# auxboxshield1_54.net
KiCad netlist of a schematic drawn in EAGLE
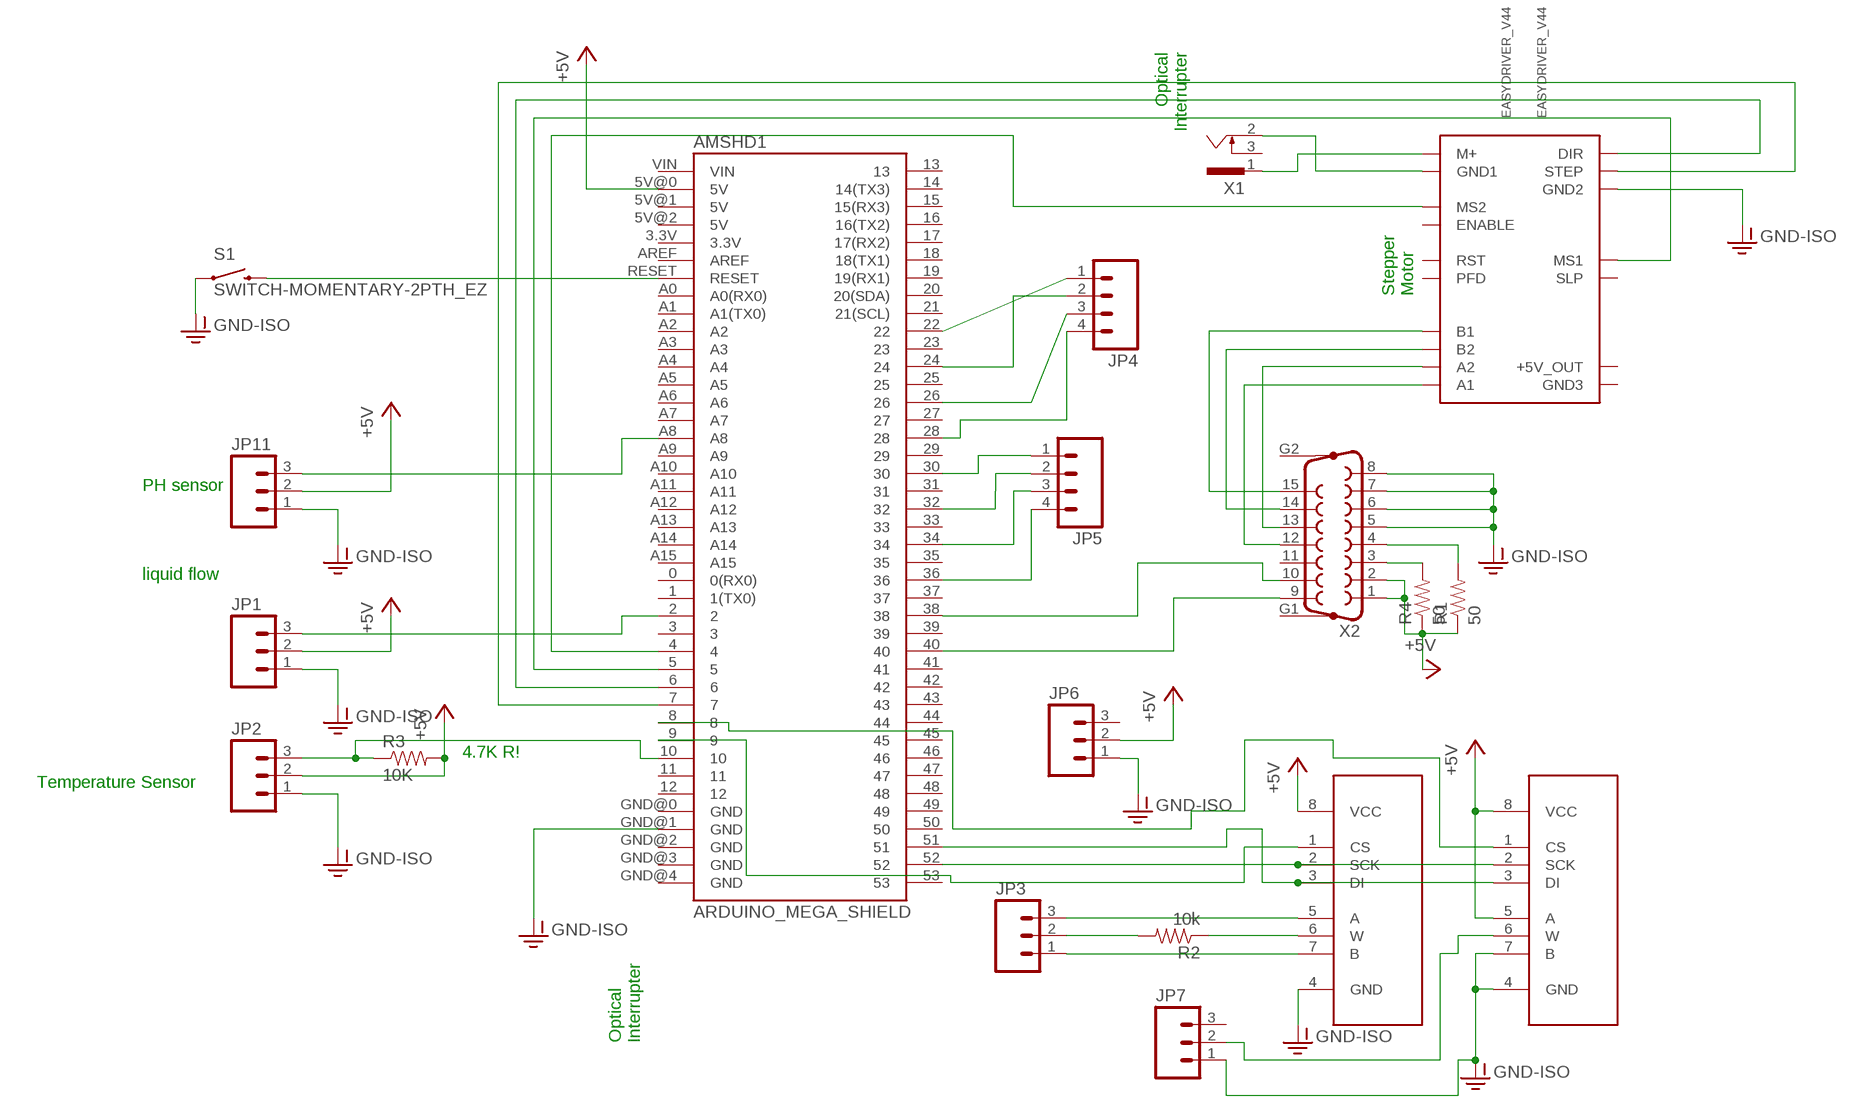
[diagram p0: schematic, sheet 1]

(export (version "E")
  (design (tool "Eeschema 10.0.6"))
  (components
    (comp (ref "AMSHD1")
      (value "ARDUINO_MEGA_SHIELD")
      (footprint "eagle-import:ARDUINO_MEGA_SHIELD")
      (libsource (lib "eagle-import") (part "ARDUINO_MEGA_SHIELD"))
    )
    (comp (ref "EASYDRIVER_V44")
      (value "EASYDRIVER_V44")
      (footprint "eagle-import:EASYDRIVER_V44")
      (libsource (lib "eagle-import") (part "EASYDRIVER_V44"))
    )
    (comp (ref "JP1")
      (value "M03POLAR")
      (footprint "eagle-import:MOLEX-1X3")
      (libsource (lib "eagle-import") (part "M03POLAR"))
    )
    (comp (ref "JP2")
      (value "M03POLAR")
      (footprint "eagle-import:MOLEX-1X3")
      (libsource (lib "eagle-import") (part "M03POLAR"))
    )
    (comp (ref "JP3")
      (value "M03POLAR")
      (footprint "eagle-import:MOLEX-1X3")
      (libsource (lib "eagle-import") (part "M03POLAR"))
    )
    (comp (ref "JP4")
      (value "M04POLAR")
      (footprint "eagle-import:MOLEX-1X4")
      (libsource (lib "eagle-import") (part "M04POLAR"))
    )
    (comp (ref "JP5")
      (value "M04POLAR")
      (footprint "eagle-import:MOLEX-1X4")
      (libsource (lib "eagle-import") (part "M04POLAR"))
    )
    (comp (ref "JP6")
      (value "M03POLAR")
      (footprint "eagle-import:MOLEX-1X3")
      (libsource (lib "eagle-import") (part "M03POLAR"))
    )
    (comp (ref "JP7")
      (value "M03POLAR")
      (footprint "eagle-import:MOLEX-1X3")
      (libsource (lib "eagle-import") (part "M03POLAR"))
    )
    (comp (ref "JP11")
      (value "M03POLAR")
      (footprint "eagle-import:MOLEX-1X3")
      (libsource (lib "eagle-import") (part "M03POLAR"))
    )
    (comp (ref "R1")
      (value "50")
      (footprint "eagle-import:AXIAL-0.3")
      (libsource (lib "eagle-import") (part "10OHM-1/4W-5%(PTH)"))
    )
    (comp (ref "R2")
      (value "10k")
      (footprint "eagle-import:AXIAL-0.3")
      (libsource (lib "eagle-import") (part "10KOHM-1/4W-1%(PTH)HORIZ"))
    )
    (comp (ref "R3")
      (value "10K")
      (footprint "eagle-import:AXIAL-0.3")
      (libsource (lib "eagle-import") (part "10OHM-1/4W-5%(PTH)"))
    )
    (comp (ref "R4")
      (value "50")
      (footprint "eagle-import:AXIAL-0.3")
      (libsource (lib "eagle-import") (part "10OHM-1/4W-5%(PTH)"))
    )
    (comp (ref "S1")
      (value "SWITCH-MOMENTARY-2PTH_EZ")
      (footprint "eagle-import:TACTILE-PTH-EZ")
      (libsource (lib "eagle-import") (part "SWITCH-MOMENTARY-2PTH_EZ"))
    )
    (comp (ref "U1")
      (value "MCP41XXXDIL")
      (footprint "eagle-import:DIL-08")
      (libsource (lib "eagle-import") (part "MCP41XXXDIL"))
    )
    (comp (ref "U2")
      (value "MCP41XXXDIL")
      (footprint "eagle-import:DIL-08")
      (libsource (lib "eagle-import") (part "MCP41XXXDIL"))
    )
    (comp (ref "X1")
      (value "SCD-014A")
      (footprint "eagle-import:SCD-014-A")
      (libsource (lib "eagle-import") (part "SCD-014A"))
    )
    (comp (ref "X2")
      (value "F15VP")
      (footprint "eagle-import:F15VP")
      (libsource (lib "eagle-import") (part "F15VP"))
    )
  )
  (nets
    (net (code "1") (name "+5V") (class "Default")
      (node (ref "AMSHD1") (pin "5V@0") (pinfunction "5V_5V@0") (pintype "bidirectional"))
      (node (ref "JP1") (pin "2") (pinfunction "2_2") (pintype "passive"))
      (node (ref "JP11") (pin "2") (pinfunction "2_2") (pintype "passive"))
      (node (ref "JP2") (pin "2") (pinfunction "2_2") (pintype "passive"))
      (node (ref "JP6") (pin "2") (pinfunction "2_2") (pintype "passive"))
      (node (ref "R1") (pin "P$1") (pinfunction "1_P$1") (pintype "passive"))
      (node (ref "R3") (pin "P$2") (pinfunction "2_P$2") (pintype "passive"))
      (node (ref "R4") (pin "P$1") (pinfunction "1_P$1") (pintype "passive"))
      (node (ref "U1") (pin "5") (pinfunction "A_5") (pintype "bidirectional"))
      (node (ref "U1") (pin "8") (pinfunction "VCC_8") (pintype "bidirectional"))
      (node (ref "U2") (pin "8") (pinfunction "VCC_8") (pintype "bidirectional"))
      (node (ref "X2") (pin "1") (pinfunction "1_1") (pintype "passive"))
      (node (ref "X2") (pin "2") (pinfunction "2_2") (pintype "passive"))
    )
    (net (code "2") (name "GND-ISO") (class "Default")
      (node (ref "AMSHD1") (pin "GND@1") (pinfunction "GND_GND@1") (pintype "bidirectional"))
      (node (ref "EASYDRIVER_V44") (pin "GND2") (pinfunction "GND2_GND2") (pintype "bidirectional"))
      (node (ref "JP1") (pin "1") (pinfunction "1_1") (pintype "passive"))
      (node (ref "JP11") (pin "1") (pinfunction "1_1") (pintype "passive"))
      (node (ref "JP2") (pin "1") (pinfunction "1_1") (pintype "passive"))
      (node (ref "JP6") (pin "1") (pinfunction "1_1") (pintype "passive"))
      (node (ref "JP7") (pin "1") (pinfunction "1_1") (pintype "passive"))
      (node (ref "S1") (pin "1") (pinfunction "1_1") (pintype "passive"))
      (node (ref "U1") (pin "4") (pinfunction "GND_4") (pintype "bidirectional"))
      (node (ref "U1") (pin "7") (pinfunction "B_7") (pintype "bidirectional"))
      (node (ref "U2") (pin "4") (pinfunction "GND_4") (pintype "bidirectional"))
      (node (ref "X2") (pin "5") (pinfunction "5_5") (pintype "passive"))
      (node (ref "X2") (pin "6") (pinfunction "6_6") (pintype "passive"))
      (node (ref "X2") (pin "7") (pinfunction "7_7") (pintype "passive"))
      (node (ref "X2") (pin "8") (pinfunction "8_8") (pintype "passive"))
    )
    (net (code "3") (name "Net-(AMSHD1-Pad2)") (class "Default")
      (node (ref "AMSHD1") (pin "2") (pinfunction "2_2") (pintype "bidirectional"))
      (node (ref "JP1") (pin "3") (pinfunction "3_3") (pintype "passive"))
    )
    (net (code "4") (name "Net-(AMSHD1-Pad4)") (class "Default")
      (node (ref "AMSHD1") (pin "4") (pinfunction "4_4") (pintype "bidirectional"))
      (node (ref "EASYDRIVER_V44") (pin "MS2") (pinfunction "MS2_MS2") (pintype "bidirectional"))
    )
    (net (code "5") (name "Net-(AMSHD1-Pad5)") (class "Default")
      (node (ref "AMSHD1") (pin "5") (pinfunction "5_5") (pintype "bidirectional"))
      (node (ref "EASYDRIVER_V44") (pin "MS1") (pinfunction "MS1_MS1") (pintype "bidirectional"))
    )
    (net (code "6") (name "Net-(AMSHD1-Pad6)") (class "Default")
      (node (ref "AMSHD1") (pin "6") (pinfunction "6_6") (pintype "bidirectional"))
      (node (ref "EASYDRIVER_V44") (pin "DIR") (pinfunction "DIR_DIR") (pintype "bidirectional"))
    )
    (net (code "7") (name "Net-(AMSHD1-Pad7)") (class "Default")
      (node (ref "AMSHD1") (pin "7") (pinfunction "7_7") (pintype "bidirectional"))
      (node (ref "EASYDRIVER_V44") (pin "STEP") (pinfunction "STEP_STEP") (pintype "bidirectional"))
    )
    (net (code "8") (name "Net-(AMSHD1-Pad22)") (class "Default")
      (node (ref "AMSHD1") (pin "22") (pinfunction "22_22") (pintype "bidirectional"))
      (node (ref "JP4") (pin "1") (pinfunction "1_1") (pintype "passive"))
    )
    (net (code "9") (name "Net-(AMSHD1-Pad24)") (class "Default")
      (node (ref "AMSHD1") (pin "24") (pinfunction "24_24") (pintype "bidirectional"))
      (node (ref "JP4") (pin "2") (pinfunction "2_2") (pintype "passive"))
    )
    (net (code "10") (name "Net-(AMSHD1-Pad26)") (class "Default")
      (node (ref "AMSHD1") (pin "26") (pinfunction "26_26") (pintype "bidirectional"))
      (node (ref "JP4") (pin "3") (pinfunction "3_3") (pintype "passive"))
    )
    (net (code "11") (name "Net-(AMSHD1-Pad28)") (class "Default")
      (node (ref "AMSHD1") (pin "28") (pinfunction "28_28") (pintype "bidirectional"))
      (node (ref "JP4") (pin "4") (pinfunction "4_4") (pintype "passive"))
    )
    (net (code "12") (name "Net-(AMSHD1-Pad30)") (class "Default")
      (node (ref "AMSHD1") (pin "30") (pinfunction "30_30") (pintype "bidirectional"))
      (node (ref "JP5") (pin "1") (pinfunction "1_1") (pintype "passive"))
    )
    (net (code "13") (name "Net-(AMSHD1-Pad32)") (class "Default")
      (node (ref "AMSHD1") (pin "32") (pinfunction "32_32") (pintype "bidirectional"))
      (node (ref "JP5") (pin "2") (pinfunction "2_2") (pintype "passive"))
    )
    (net (code "14") (name "Net-(AMSHD1-Pad34)") (class "Default")
      (node (ref "AMSHD1") (pin "34") (pinfunction "34_34") (pintype "bidirectional"))
      (node (ref "JP5") (pin "3") (pinfunction "3_3") (pintype "passive"))
    )
    (net (code "15") (name "Net-(AMSHD1-Pad36)") (class "Default")
      (node (ref "AMSHD1") (pin "36") (pinfunction "36_36") (pintype "bidirectional"))
      (node (ref "JP5") (pin "4") (pinfunction "4_4") (pintype "passive"))
    )
    (net (code "16") (name "Net-(AMSHD1-Pad38)") (class "Default")
      (node (ref "AMSHD1") (pin "38") (pinfunction "38_38") (pintype "bidirectional"))
      (node (ref "X2") (pin "10") (pinfunction "10_10") (pintype "passive"))
    )
    (net (code "17") (name "Net-(AMSHD1-Pad40)") (class "Default")
      (node (ref "AMSHD1") (pin "40") (pinfunction "40_40") (pintype "bidirectional"))
      (node (ref "X2") (pin "9") (pinfunction "9_9") (pintype "passive"))
    )
    (net (code "18") (name "Net-(AMSHD1-PadA8)") (class "Default")
      (node (ref "AMSHD1") (pin "A8") (pinfunction "A8_A8") (pintype "bidirectional"))
      (node (ref "JP11") (pin "3") (pinfunction "3_3") (pintype "passive"))
    )
    (net (code "19") (name "Net-(EASYDRIVER_V44-PadA1)") (class "Default")
      (node (ref "EASYDRIVER_V44") (pin "A1") (pinfunction "A1_A1") (pintype "bidirectional"))
      (node (ref "X2") (pin "12") (pinfunction "12_12") (pintype "passive"))
    )
    (net (code "20") (name "Net-(EASYDRIVER_V44-PadA2)") (class "Default")
      (node (ref "EASYDRIVER_V44") (pin "A2") (pinfunction "A2_A2") (pintype "bidirectional"))
      (node (ref "X2") (pin "13") (pinfunction "13_13") (pintype "passive"))
    )
    (net (code "21") (name "Net-(EASYDRIVER_V44-PadB1)") (class "Default")
      (node (ref "EASYDRIVER_V44") (pin "B1") (pinfunction "B1_B1") (pintype "bidirectional"))
      (node (ref "X2") (pin "15") (pinfunction "15_15") (pintype "passive"))
    )
    (net (code "22") (name "Net-(EASYDRIVER_V44-PadB2)") (class "Default")
      (node (ref "EASYDRIVER_V44") (pin "B2") (pinfunction "B2_B2") (pintype "bidirectional"))
      (node (ref "X2") (pin "14") (pinfunction "14_14") (pintype "passive"))
    )
    (net (code "23") (name "Net-(EASYDRIVER_V44-PadGND1)") (class "Default")
      (node (ref "EASYDRIVER_V44") (pin "GND1") (pinfunction "GND1_GND1") (pintype "bidirectional"))
      (node (ref "X1") (pin "2") (pinfunction "2_2") (pintype "passive"))
    )
    (net (code "24") (name "Net-(EASYDRIVER_V44-PadM+)") (class "Default")
      (node (ref "EASYDRIVER_V44") (pin "M+") (pinfunction "M+_M+") (pintype "bidirectional"))
      (node (ref "X1") (pin "1") (pinfunction "1_1") (pintype "passive"))
    )
    (net (code "25") (name "Net-(R1-2)") (class "Default")
      (node (ref "R1") (pin "P$2") (pinfunction "2_P$2") (pintype "passive"))
      (node (ref "X2") (pin "4") (pinfunction "4_4") (pintype "passive"))
    )
    (net (code "26") (name "Net-(R2-1)") (class "Default")
      (node (ref "R2") (pin "P$1") (pinfunction "1_P$1") (pintype "passive"))
      (node (ref "U2") (pin "6") (pinfunction "W_6") (pintype "bidirectional"))
    )
    (net (code "27") (name "Net-(R2-2)") (class "Default")
      (node (ref "JP3") (pin "2") (pinfunction "2_2") (pintype "passive"))
      (node (ref "R2") (pin "P$2") (pinfunction "2_P$2") (pintype "passive"))
    )
    (net (code "28") (name "Net-(R3-1)") (class "Default")
      (node (ref "AMSHD1") (pin "10") (pinfunction "10_10") (pintype "bidirectional"))
      (node (ref "JP2") (pin "3") (pinfunction "3_3") (pintype "passive"))
      (node (ref "R3") (pin "P$1") (pinfunction "1_P$1") (pintype "passive"))
    )
    (net (code "29") (name "Net-(R4-2)") (class "Default")
      (node (ref "R4") (pin "P$2") (pinfunction "2_P$2") (pintype "passive"))
      (node (ref "X2") (pin "3") (pinfunction "3_3") (pintype "passive"))
    )
    (net (code "30") (name "Net-(S1-2)") (class "Default")
      (node (ref "AMSHD1") (pin "RESET") (pinfunction "RESET_RESET") (pintype "bidirectional"))
      (node (ref "S1") (pin "3") (pinfunction "2_3") (pintype "passive"))
    )
    (net (code "31") (name "Net-(U1-CS)") (class "Default")
      (node (ref "AMSHD1") (pin "8") (pinfunction "8_8") (pintype "bidirectional"))
      (node (ref "U1") (pin "1") (pinfunction "CS_1") (pintype "bidirectional"))
    )
    (net (code "32") (name "Net-(U1-DI)") (class "Default")
      (node (ref "AMSHD1") (pin "51") (pinfunction "51_51") (pintype "bidirectional"))
      (node (ref "U1") (pin "3") (pinfunction "DI_3") (pintype "bidirectional"))
      (node (ref "U2") (pin "3") (pinfunction "DI_3") (pintype "bidirectional"))
    )
    (net (code "33") (name "Net-(U1-SCK)") (class "Default")
      (node (ref "AMSHD1") (pin "52") (pinfunction "52_52") (pintype "bidirectional"))
      (node (ref "U1") (pin "2") (pinfunction "SCK_2") (pintype "bidirectional"))
      (node (ref "U2") (pin "2") (pinfunction "SCK_2") (pintype "bidirectional"))
    )
    (net (code "34") (name "Net-(U1-W)") (class "Default")
      (node (ref "JP7") (pin "2") (pinfunction "2_2") (pintype "passive"))
      (node (ref "U1") (pin "6") (pinfunction "W_6") (pintype "bidirectional"))
    )
    (net (code "35") (name "Net-(U2-A)") (class "Default")
      (node (ref "JP3") (pin "3") (pinfunction "3_3") (pintype "passive"))
      (node (ref "U2") (pin "5") (pinfunction "A_5") (pintype "bidirectional"))
    )
    (net (code "36") (name "Net-(U2-B)") (class "Default")
      (node (ref "JP3") (pin "1") (pinfunction "1_1") (pintype "passive"))
      (node (ref "U2") (pin "7") (pinfunction "B_7") (pintype "bidirectional"))
    )
    (net (code "37") (name "Net-(U2-CS)") (class "Default")
      (node (ref "AMSHD1") (pin "9") (pinfunction "9_9") (pintype "bidirectional"))
      (node (ref "U2") (pin "1") (pinfunction "CS_1") (pintype "bidirectional"))
    )
    (net (code "38") (name "unconnected-(AMSHD1-0(RX0)-Pad0)") (class "Default")
      (node (ref "AMSHD1") (pin "0") (pinfunction "0(RX0)_0") (pintype "bidirectional"))
    )
    (net (code "39") (name "unconnected-(AMSHD1-1(TX0)-Pad1)") (class "Default")
      (node (ref "AMSHD1") (pin "1") (pinfunction "1(TX0)_1") (pintype "bidirectional"))
    )
    (net (code "40") (name "unconnected-(AMSHD1-5V-Pad5V@1)") (class "Default")
      (node (ref "AMSHD1") (pin "5V@1") (pinfunction "5V_5V@1") (pintype "bidirectional"))
    )
    (net (code "41") (name "unconnected-(AMSHD1-5V-Pad5V@2)") (class "Default")
      (node (ref "AMSHD1") (pin "5V@2") (pinfunction "5V_5V@2") (pintype "bidirectional"))
    )
    (net (code "42") (name "unconnected-(AMSHD1-14(TX3)-Pad14)") (class "Default")
      (node (ref "AMSHD1") (pin "14") (pinfunction "14(TX3)_14") (pintype "bidirectional"))
    )
    (net (code "43") (name "unconnected-(AMSHD1-15(RX3)-Pad15)") (class "Default")
      (node (ref "AMSHD1") (pin "15") (pinfunction "15(RX3)_15") (pintype "bidirectional"))
    )
    (net (code "44") (name "unconnected-(AMSHD1-16(TX2)-Pad16)") (class "Default")
      (node (ref "AMSHD1") (pin "16") (pinfunction "16(TX2)_16") (pintype "bidirectional"))
    )
    (net (code "45") (name "unconnected-(AMSHD1-17(RX2)-Pad17)") (class "Default")
      (node (ref "AMSHD1") (pin "17") (pinfunction "17(RX2)_17") (pintype "bidirectional"))
    )
    (net (code "46") (name "unconnected-(AMSHD1-18(TX1)-Pad18)") (class "Default")
      (node (ref "AMSHD1") (pin "18") (pinfunction "18(TX1)_18") (pintype "bidirectional"))
    )
    (net (code "47") (name "unconnected-(AMSHD1-19(RX1)-Pad19)") (class "Default")
      (node (ref "AMSHD1") (pin "19") (pinfunction "19(RX1)_19") (pintype "bidirectional"))
    )
    (net (code "48") (name "unconnected-(AMSHD1-20(SDA)-Pad20)") (class "Default")
      (node (ref "AMSHD1") (pin "20") (pinfunction "20(SDA)_20") (pintype "bidirectional"))
    )
    (net (code "49") (name "unconnected-(AMSHD1-21(SCL)-Pad21)") (class "Default")
      (node (ref "AMSHD1") (pin "21") (pinfunction "21(SCL)_21") (pintype "bidirectional"))
    )
    (net (code "50") (name "unconnected-(AMSHD1-A0(RX0)-PadA0)") (class "Default")
      (node (ref "AMSHD1") (pin "A0") (pinfunction "A0(RX0)_A0") (pintype "bidirectional"))
    )
    (net (code "51") (name "unconnected-(AMSHD1-A1(TX0)-PadA1)") (class "Default")
      (node (ref "AMSHD1") (pin "A1") (pinfunction "A1(TX0)_A1") (pintype "bidirectional"))
    )
    (net (code "52") (name "unconnected-(AMSHD1-GND-PadGND@0)") (class "Default")
      (node (ref "AMSHD1") (pin "GND@0") (pinfunction "GND_GND@0") (pintype "bidirectional"))
    )
    (net (code "53") (name "unconnected-(AMSHD1-GND-PadGND@2)") (class "Default")
      (node (ref "AMSHD1") (pin "GND@2") (pinfunction "GND_GND@2") (pintype "bidirectional"))
    )
    (net (code "54") (name "unconnected-(AMSHD1-GND-PadGND@3)") (class "Default")
      (node (ref "AMSHD1") (pin "GND@3") (pinfunction "GND_GND@3") (pintype "bidirectional"))
    )
    (net (code "55") (name "unconnected-(AMSHD1-GND-PadGND@4)") (class "Default")
      (node (ref "AMSHD1") (pin "GND@4") (pinfunction "GND_GND@4") (pintype "bidirectional"))
    )
    (net (code "56") (name "unconnected-(AMSHD1-Pad3)") (class "Default")
      (node (ref "AMSHD1") (pin "3") (pinfunction "3_3") (pintype "bidirectional"))
    )
    (net (code "57") (name "unconnected-(AMSHD1-Pad3.3V)") (class "Default")
      (node (ref "AMSHD1") (pin "3.3V") (pinfunction "3.3V_3.3V") (pintype "bidirectional"))
    )
    (net (code "58") (name "unconnected-(AMSHD1-Pad11)") (class "Default")
      (node (ref "AMSHD1") (pin "11") (pinfunction "11_11") (pintype "bidirectional"))
    )
    (net (code "59") (name "unconnected-(AMSHD1-Pad12)") (class "Default")
      (node (ref "AMSHD1") (pin "12") (pinfunction "12_12") (pintype "bidirectional"))
    )
    (net (code "60") (name "unconnected-(AMSHD1-Pad13)") (class "Default")
      (node (ref "AMSHD1") (pin "13") (pinfunction "13_13") (pintype "bidirectional"))
    )
    (net (code "61") (name "unconnected-(AMSHD1-Pad23)") (class "Default")
      (node (ref "AMSHD1") (pin "23") (pinfunction "23_23") (pintype "bidirectional"))
    )
    (net (code "62") (name "unconnected-(AMSHD1-Pad25)") (class "Default")
      (node (ref "AMSHD1") (pin "25") (pinfunction "25_25") (pintype "bidirectional"))
    )
    (net (code "63") (name "unconnected-(AMSHD1-Pad27)") (class "Default")
      (node (ref "AMSHD1") (pin "27") (pinfunction "27_27") (pintype "bidirectional"))
    )
    (net (code "64") (name "unconnected-(AMSHD1-Pad29)") (class "Default")
      (node (ref "AMSHD1") (pin "29") (pinfunction "29_29") (pintype "bidirectional"))
    )
    (net (code "65") (name "unconnected-(AMSHD1-Pad31)") (class "Default")
      (node (ref "AMSHD1") (pin "31") (pinfunction "31_31") (pintype "bidirectional"))
    )
    (net (code "66") (name "unconnected-(AMSHD1-Pad33)") (class "Default")
      (node (ref "AMSHD1") (pin "33") (pinfunction "33_33") (pintype "bidirectional"))
    )
    (net (code "67") (name "unconnected-(AMSHD1-Pad35)") (class "Default")
      (node (ref "AMSHD1") (pin "35") (pinfunction "35_35") (pintype "bidirectional"))
    )
    (net (code "68") (name "unconnected-(AMSHD1-Pad37)") (class "Default")
      (node (ref "AMSHD1") (pin "37") (pinfunction "37_37") (pintype "bidirectional"))
    )
    (net (code "69") (name "unconnected-(AMSHD1-Pad39)") (class "Default")
      (node (ref "AMSHD1") (pin "39") (pinfunction "39_39") (pintype "bidirectional"))
    )
    (net (code "70") (name "unconnected-(AMSHD1-Pad41)") (class "Default")
      (node (ref "AMSHD1") (pin "41") (pinfunction "41_41") (pintype "bidirectional"))
    )
    (net (code "71") (name "unconnected-(AMSHD1-Pad42)") (class "Default")
      (node (ref "AMSHD1") (pin "42") (pinfunction "42_42") (pintype "bidirectional"))
    )
    (net (code "72") (name "unconnected-(AMSHD1-Pad43)") (class "Default")
      (node (ref "AMSHD1") (pin "43") (pinfunction "43_43") (pintype "bidirectional"))
    )
    (net (code "73") (name "unconnected-(AMSHD1-Pad44)") (class "Default")
      (node (ref "AMSHD1") (pin "44") (pinfunction "44_44") (pintype "bidirectional"))
    )
    (net (code "74") (name "unconnected-(AMSHD1-Pad45)") (class "Default")
      (node (ref "AMSHD1") (pin "45") (pinfunction "45_45") (pintype "bidirectional"))
    )
    (net (code "75") (name "unconnected-(AMSHD1-Pad46)") (class "Default")
      (node (ref "AMSHD1") (pin "46") (pinfunction "46_46") (pintype "bidirectional"))
    )
    (net (code "76") (name "unconnected-(AMSHD1-Pad47)") (class "Default")
      (node (ref "AMSHD1") (pin "47") (pinfunction "47_47") (pintype "bidirectional"))
    )
    (net (code "77") (name "unconnected-(AMSHD1-Pad48)") (class "Default")
      (node (ref "AMSHD1") (pin "48") (pinfunction "48_48") (pintype "bidirectional"))
    )
    (net (code "78") (name "unconnected-(AMSHD1-Pad49)") (class "Default")
      (node (ref "AMSHD1") (pin "49") (pinfunction "49_49") (pintype "bidirectional"))
    )
    (net (code "79") (name "unconnected-(AMSHD1-Pad50)") (class "Default")
      (node (ref "AMSHD1") (pin "50") (pinfunction "50_50") (pintype "bidirectional"))
    )
    (net (code "80") (name "unconnected-(AMSHD1-Pad53)") (class "Default")
      (node (ref "AMSHD1") (pin "53") (pinfunction "53_53") (pintype "bidirectional"))
    )
    (net (code "81") (name "unconnected-(AMSHD1-PadA2)") (class "Default")
      (node (ref "AMSHD1") (pin "A2") (pinfunction "A2_A2") (pintype "bidirectional"))
    )
    (net (code "82") (name "unconnected-(AMSHD1-PadA3)") (class "Default")
      (node (ref "AMSHD1") (pin "A3") (pinfunction "A3_A3") (pintype "bidirectional"))
    )
    (net (code "83") (name "unconnected-(AMSHD1-PadA4)") (class "Default")
      (node (ref "AMSHD1") (pin "A4") (pinfunction "A4_A4") (pintype "bidirectional"))
    )
    (net (code "84") (name "unconnected-(AMSHD1-PadA5)") (class "Default")
      (node (ref "AMSHD1") (pin "A5") (pinfunction "A5_A5") (pintype "bidirectional"))
    )
    (net (code "85") (name "unconnected-(AMSHD1-PadA6)") (class "Default")
      (node (ref "AMSHD1") (pin "A6") (pinfunction "A6_A6") (pintype "bidirectional"))
    )
    (net (code "86") (name "unconnected-(AMSHD1-PadA7)") (class "Default")
      (node (ref "AMSHD1") (pin "A7") (pinfunction "A7_A7") (pintype "bidirectional"))
    )
    (net (code "87") (name "unconnected-(AMSHD1-PadA9)") (class "Default")
      (node (ref "AMSHD1") (pin "A9") (pinfunction "A9_A9") (pintype "bidirectional"))
    )
    (net (code "88") (name "unconnected-(AMSHD1-PadA10)") (class "Default")
      (node (ref "AMSHD1") (pin "A10") (pinfunction "A10_A10") (pintype "bidirectional"))
    )
    (net (code "89") (name "unconnected-(AMSHD1-PadA11)") (class "Default")
      (node (ref "AMSHD1") (pin "A11") (pinfunction "A11_A11") (pintype "bidirectional"))
    )
    (net (code "90") (name "unconnected-(AMSHD1-PadA12)") (class "Default")
      (node (ref "AMSHD1") (pin "A12") (pinfunction "A12_A12") (pintype "bidirectional"))
    )
    (net (code "91") (name "unconnected-(AMSHD1-PadA13)") (class "Default")
      (node (ref "AMSHD1") (pin "A13") (pinfunction "A13_A13") (pintype "bidirectional"))
    )
    (net (code "92") (name "unconnected-(AMSHD1-PadA14)") (class "Default")
      (node (ref "AMSHD1") (pin "A14") (pinfunction "A14_A14") (pintype "bidirectional"))
    )
    (net (code "93") (name "unconnected-(AMSHD1-PadA15)") (class "Default")
      (node (ref "AMSHD1") (pin "A15") (pinfunction "A15_A15") (pintype "bidirectional"))
    )
    (net (code "94") (name "unconnected-(AMSHD1-PadAREF)") (class "Default")
      (node (ref "AMSHD1") (pin "AREF") (pinfunction "AREF_AREF") (pintype "bidirectional"))
    )
    (net (code "95") (name "unconnected-(AMSHD1-PadVIN)") (class "Default")
      (node (ref "AMSHD1") (pin "VIN") (pinfunction "VIN_VIN") (pintype "bidirectional"))
    )
    (net (code "96") (name "unconnected-(EASYDRIVER_V44-+5V_OUT-PadP$11)") (class "Default")
      (node (ref "EASYDRIVER_V44") (pin "P$11") (pinfunction "+5V_OUT_P$11") (pintype "bidirectional"))
    )
    (net (code "97") (name "unconnected-(EASYDRIVER_V44-PadENABLE)") (class "Default")
      (node (ref "EASYDRIVER_V44") (pin "ENABLE") (pinfunction "ENABLE_ENABLE") (pintype "bidirectional"))
    )
    (net (code "98") (name "unconnected-(EASYDRIVER_V44-PadGND3)") (class "Default")
      (node (ref "EASYDRIVER_V44") (pin "GND3") (pinfunction "GND3_GND3") (pintype "bidirectional"))
    )
    (net (code "99") (name "unconnected-(EASYDRIVER_V44-PadPFD)") (class "Default")
      (node (ref "EASYDRIVER_V44") (pin "PFD") (pinfunction "PFD_PFD") (pintype "bidirectional"))
    )
    (net (code "100") (name "unconnected-(EASYDRIVER_V44-PadRST)") (class "Default")
      (node (ref "EASYDRIVER_V44") (pin "RST") (pinfunction "RST_RST") (pintype "bidirectional"))
    )
    (net (code "101") (name "unconnected-(EASYDRIVER_V44-SLP-PadSLEEP)") (class "Default")
      (node (ref "EASYDRIVER_V44") (pin "SLEEP") (pinfunction "SLP_SLEEP") (pintype "bidirectional"))
    )
    (net (code "102") (name "unconnected-(JP6-Pad3)") (class "Default")
      (node (ref "JP6") (pin "3") (pinfunction "3_3") (pintype "passive"))
    )
    (net (code "103") (name "unconnected-(JP7-Pad3)") (class "Default")
      (node (ref "JP7") (pin "3") (pinfunction "3_3") (pintype "passive"))
    )
    (net (code "104") (name "unconnected-(X1-Pad3)") (class "Default")
      (node (ref "X1") (pin "3") (pinfunction "3_3") (pintype "passive"))
    )
    (net (code "105") (name "unconnected-(X2-Pad11)") (class "Default")
      (node (ref "X2") (pin "11") (pinfunction "11_11") (pintype "passive"))
    )
    (net (code "106") (name "unconnected-(X2-PadG1)") (class "Default")
      (node (ref "X2") (pin "G1") (pinfunction "G1_G1") (pintype "passive"))
    )
    (net (code "107") (name "unconnected-(X2-PadG2)") (class "Default")
      (node (ref "X2") (pin "G2") (pinfunction "G2_G2") (pintype "passive"))
    )
  )
)
